# rpibout.net
KiCad netlist of a schematic drawn in EAGLE
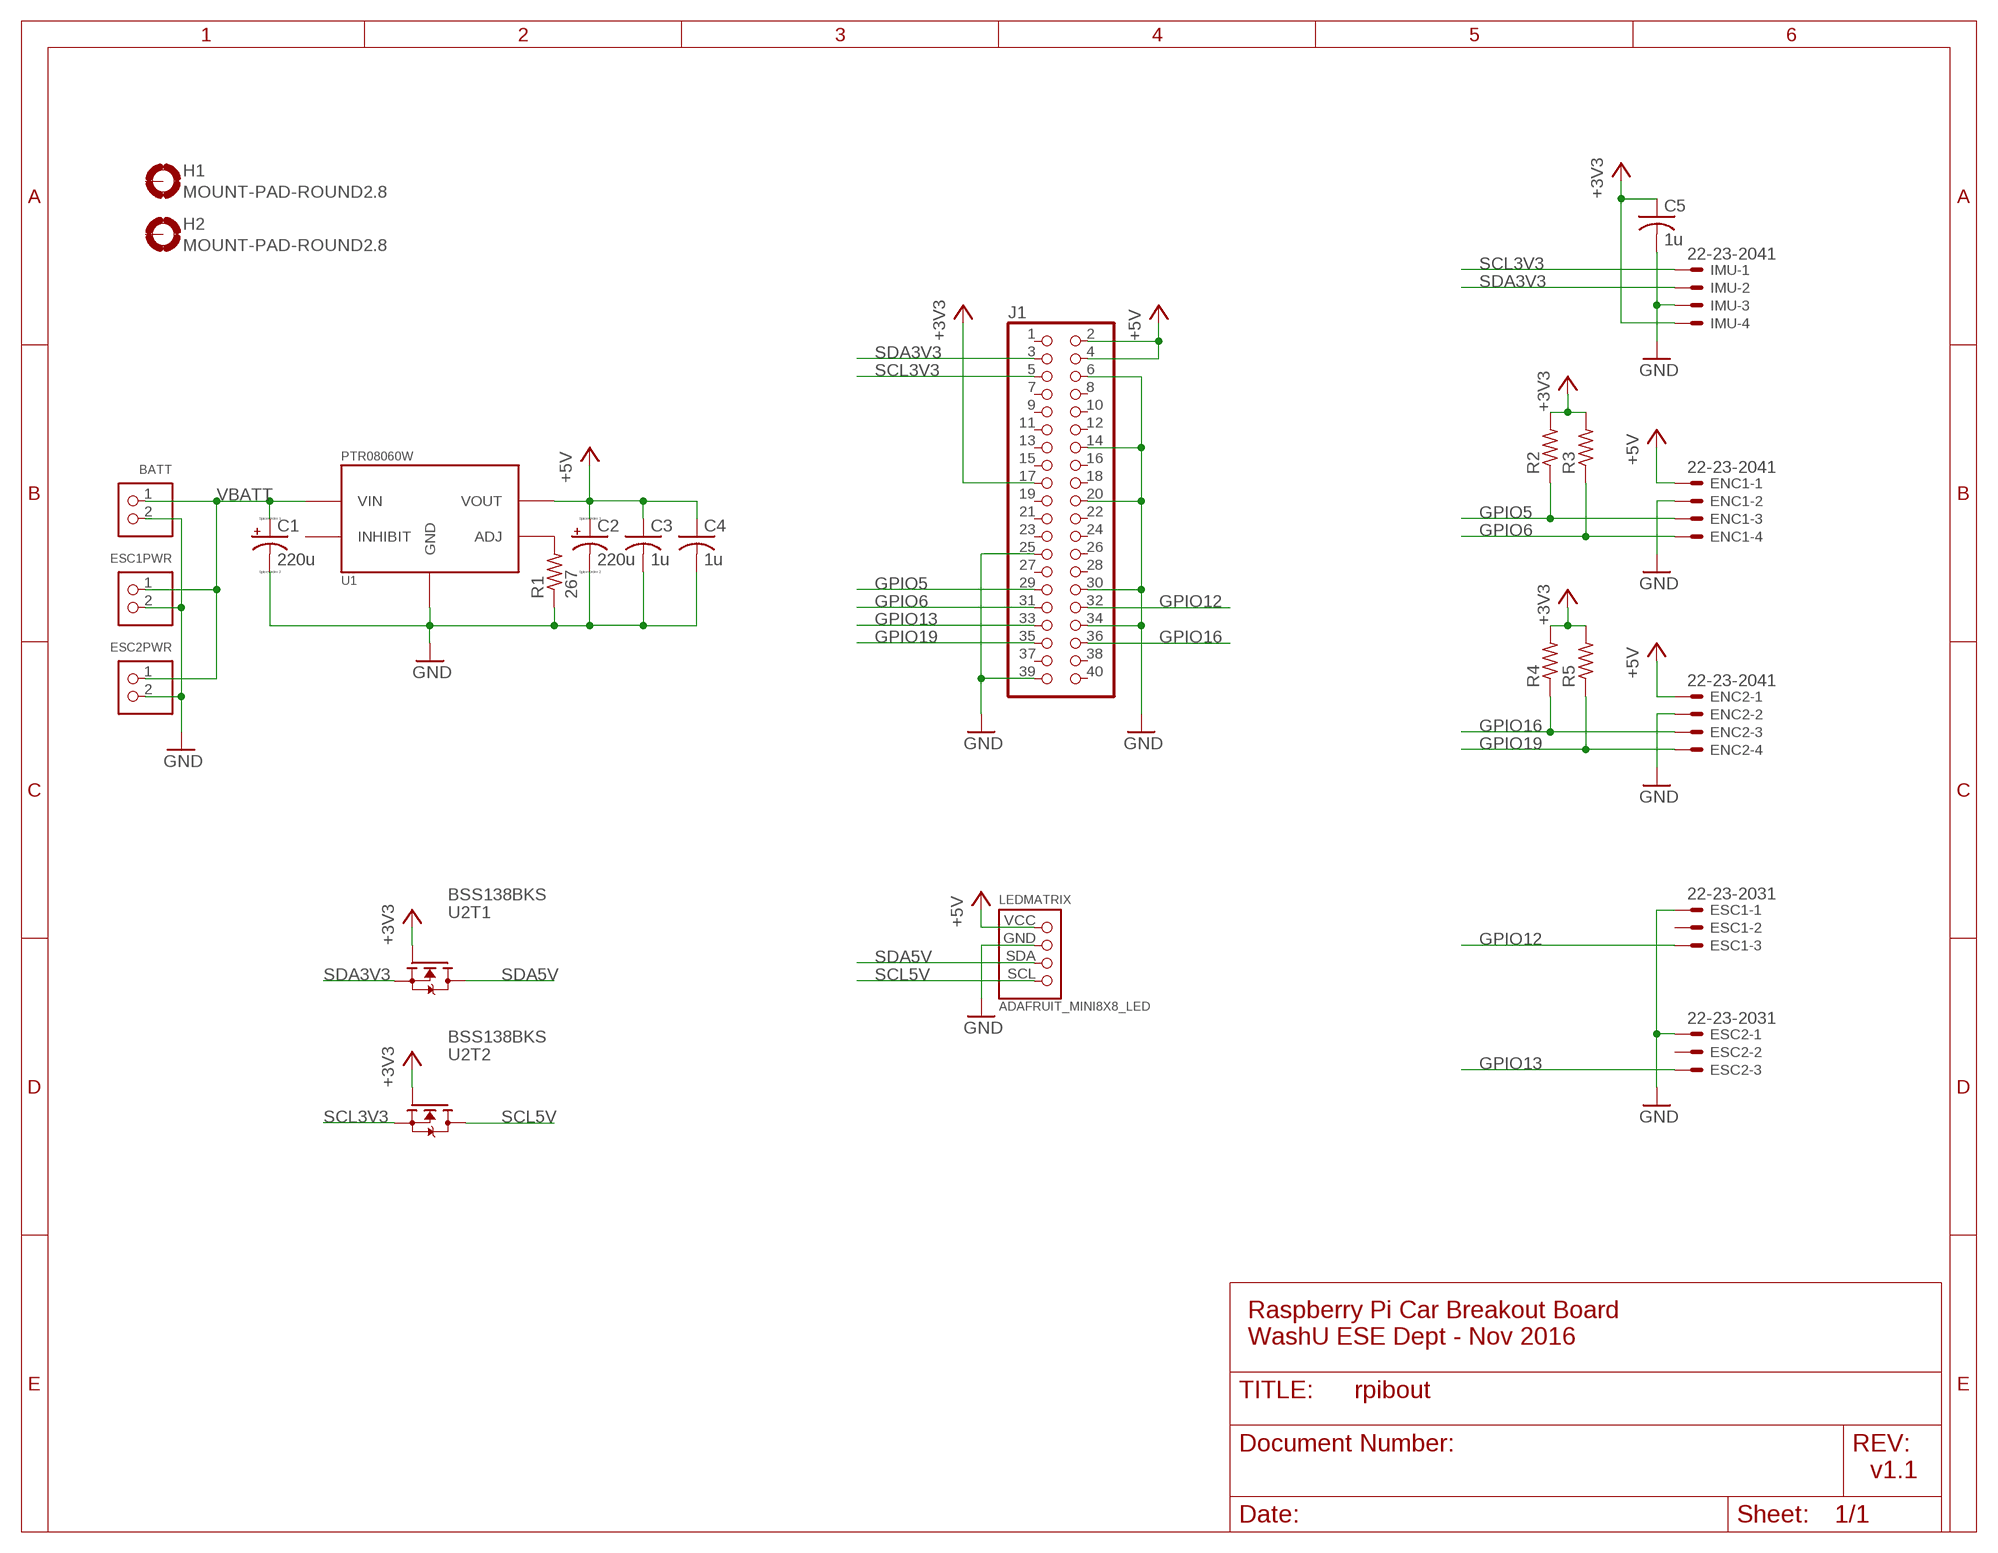
[diagram p0: schematic, sheet 1]

(export (version "E")
  (design (tool "Eeschema 10.0.6"))
  (components
    (comp (ref "BATT")
      (value "ULTRAFIT_2CIRC")
      (footprint "eagle-import:ULTRAFIT_2CIRC_RANGLE")
      (libsource (lib "eagle-import") (part "ULTRAFIT_2CIRC"))
    )
    (comp (ref "C1")
      (value "220u")
      (footprint "eagle-import:E3,5-8")
      (libsource (lib "eagle-import") (part "CPOL-USE3.5-8"))
    )
    (comp (ref "C2")
      (value "220u")
      (footprint "eagle-import:E3,5-8")
      (libsource (lib "eagle-import") (part "CPOL-USE3.5-8"))
    )
    (comp (ref "C3")
      (value "1u")
      (footprint "eagle-import:C1206")
      (libsource (lib "eagle-import") (part "C-USC1206"))
    )
    (comp (ref "C4")
      (value "1u")
      (footprint "eagle-import:C1206")
      (libsource (lib "eagle-import") (part "C-USC1206"))
    )
    (comp (ref "C5")
      (value "1u")
      (footprint "eagle-import:C1206")
      (libsource (lib "eagle-import") (part "C-USC1206"))
    )
    (comp (ref "ENC1")
      (value "22-23-2041")
      (footprint "eagle-import:22-23-2041")
      (fields (field (name "MF") "MOLEX"))
      (libsource (lib "eagle-import") (part "22-23-2041"))
    )
    (comp (ref "ENC2")
      (value "22-23-2041")
      (footprint "eagle-import:22-23-2041")
      (fields (field (name "MF") "MOLEX"))
      (libsource (lib "eagle-import") (part "22-23-2041"))
    )
    (comp (ref "ESC1")
      (value "22-23-2031")
      (footprint "eagle-import:22-23-2031")
      (fields (field (name "MF") "MOLEX"))
      (libsource (lib "eagle-import") (part "22-23-2031"))
    )
    (comp (ref "ESC1PWR")
      (value "ULTRAFIT_2CIRC")
      (footprint "eagle-import:ULTRAFIT_2CIRC_RANGLE")
      (libsource (lib "eagle-import") (part "ULTRAFIT_2CIRC"))
    )
    (comp (ref "ESC2")
      (value "22-23-2031")
      (footprint "eagle-import:22-23-2031")
      (fields (field (name "MF") "MOLEX"))
      (libsource (lib "eagle-import") (part "22-23-2031"))
    )
    (comp (ref "ESC2PWR")
      (value "ULTRAFIT_2CIRC")
      (footprint "eagle-import:ULTRAFIT_2CIRC_RANGLE")
      (libsource (lib "eagle-import") (part "ULTRAFIT_2CIRC"))
    )
    (comp (ref "H1")
      (value "MOUNT-PAD-ROUND2.8")
      (footprint "eagle-import:2,8-PAD")
      (libsource (lib "eagle-import") (part "MOUNT-PAD-ROUND2.8"))
    )
    (comp (ref "H2")
      (value "MOUNT-PAD-ROUND2.8")
      (footprint "eagle-import:2,8-PAD")
      (libsource (lib "eagle-import") (part "MOUNT-PAD-ROUND2.8"))
    )
    (comp (ref "IMU")
      (value "22-23-2041")
      (footprint "eagle-import:22-23-2041")
      (fields (field (name "MF") "MOLEX"))
      (libsource (lib "eagle-import") (part "22-23-2041"))
    )
    (comp (ref "J1")
      (value "PINHD-2X20")
      (footprint "eagle-import:2X20")
      (libsource (lib "eagle-import") (part "PINHD-2X20"))
    )
    (comp (ref "LEDMATRIX")
      (value "ADAFRUIT_MINI8X8_LED")
      (footprint "eagle-import:ADAFRUIT_MINI8X8_BACKPACK")
      (libsource (lib "eagle-import") (part "ADAFRUIT_MINI8X8_LED"))
    )
    (comp (ref "R1")
      (value "267")
      (footprint "eagle-import:R1206")
      (libsource (lib "eagle-import") (part "R-US_R1206"))
    )
    (comp (ref "R2")
      (value "R-US_R1206")
      (footprint "eagle-import:R1206")
      (libsource (lib "eagle-import") (part "R-US_R1206"))
    )
    (comp (ref "R3")
      (value "R-US_R1206")
      (footprint "eagle-import:R1206")
      (libsource (lib "eagle-import") (part "R-US_R1206"))
    )
    (comp (ref "R4")
      (value "R-US_R1206")
      (footprint "eagle-import:R1206")
      (libsource (lib "eagle-import") (part "R-US_R1206"))
    )
    (comp (ref "R5")
      (value "R-US_R1206")
      (footprint "eagle-import:R1206")
      (libsource (lib "eagle-import") (part "R-US_R1206"))
    )
    (comp (ref "U1")
      (value "PTR08060W")
      (footprint "eagle-import:EDP_MODULE")
      (libsource (lib "eagle-import") (part "PTR08060W"))
    )
    (comp (ref "U2")
      (value "BSS138BKS")
      (footprint "eagle-import:SOT363")
      (libsource (lib "eagle-import") (part "BSS138BKS"))
    )
  )
  (nets
    (net (code "1") (name "+3V3") (class "Default")
      (node (ref "C5") (pin "1") (pinfunction "1_1") (pintype "passive"))
      (node (ref "IMU") (pin "4") (pinfunction "S_4") (pintype "passive"))
      (node (ref "J1") (pin "17") (pinfunction "17_17") (pintype "passive"))
      (node (ref "R2") (pin "2") (pinfunction "2_2") (pintype "passive"))
      (node (ref "R3") (pin "2") (pinfunction "2_2") (pintype "passive"))
      (node (ref "R4") (pin "2") (pinfunction "2_2") (pintype "passive"))
      (node (ref "R5") (pin "2") (pinfunction "2_2") (pintype "passive"))
      (node (ref "U2") (pin "2") (pinfunction "G_2") (pintype "passive"))
      (node (ref "U2") (pin "5") (pinfunction "G_5") (pintype "passive"))
    )
    (net (code "2") (name "+5V") (class "Default")
      (node (ref "C2") (pin "+") (pinfunction "+_+") (pintype "passive"))
      (node (ref "C3") (pin "1") (pinfunction "1_1") (pintype "passive"))
      (node (ref "C4") (pin "1") (pinfunction "1_1") (pintype "passive"))
      (node (ref "ENC1") (pin "1") (pinfunction "S_1") (pintype "passive"))
      (node (ref "ENC2") (pin "1") (pinfunction "S_1") (pintype "passive"))
      (node (ref "J1") (pin "2") (pinfunction "2_2") (pintype "passive"))
      (node (ref "J1") (pin "4") (pinfunction "4_4") (pintype "passive"))
      (node (ref "LEDMATRIX") (pin "VCC") (pinfunction "VCC_VCC") (pintype "power_in"))
      (node (ref "U1") (pin "P4") (pinfunction "VOUT_P4") (pintype "power_in"))
    )
    (net (code "3") (name "/GPIO5") (class "Default")
      (node (ref "ENC1") (pin "3") (pinfunction "S_3") (pintype "passive"))
      (node (ref "J1") (pin "29") (pinfunction "29_29") (pintype "passive"))
      (node (ref "R2") (pin "1") (pinfunction "1_1") (pintype "passive"))
    )
    (net (code "4") (name "/GPIO6") (class "Default")
      (node (ref "ENC1") (pin "4") (pinfunction "S_4") (pintype "passive"))
      (node (ref "J1") (pin "31") (pinfunction "31_31") (pintype "passive"))
      (node (ref "R3") (pin "1") (pinfunction "1_1") (pintype "passive"))
    )
    (net (code "5") (name "/GPIO12") (class "Default")
      (node (ref "ESC1") (pin "3") (pinfunction "S_3") (pintype "passive"))
      (node (ref "J1") (pin "32") (pinfunction "32_32") (pintype "passive"))
    )
    (net (code "6") (name "/GPIO13") (class "Default")
      (node (ref "ESC2") (pin "3") (pinfunction "S_3") (pintype "passive"))
      (node (ref "J1") (pin "33") (pinfunction "33_33") (pintype "passive"))
    )
    (net (code "7") (name "/GPIO16") (class "Default")
      (node (ref "ENC2") (pin "3") (pinfunction "S_3") (pintype "passive"))
      (node (ref "J1") (pin "36") (pinfunction "36_36") (pintype "passive"))
      (node (ref "R4") (pin "1") (pinfunction "1_1") (pintype "passive"))
    )
    (net (code "8") (name "/GPIO19") (class "Default")
      (node (ref "ENC2") (pin "4") (pinfunction "S_4") (pintype "passive"))
      (node (ref "J1") (pin "35") (pinfunction "35_35") (pintype "passive"))
      (node (ref "R5") (pin "1") (pinfunction "1_1") (pintype "passive"))
    )
    (net (code "9") (name "/SCL3V3") (class "Default")
      (node (ref "IMU") (pin "1") (pinfunction "S_1") (pintype "passive"))
      (node (ref "J1") (pin "5") (pinfunction "5_5") (pintype "passive"))
      (node (ref "U2") (pin "4") (pinfunction "S_4") (pintype "passive"))
    )
    (net (code "10") (name "/SCL5V") (class "Default")
      (node (ref "LEDMATRIX") (pin "SCL") (pinfunction "SCL_SCL") (pintype "bidirectional"))
      (node (ref "U2") (pin "3") (pinfunction "D_3") (pintype "passive"))
    )
    (net (code "11") (name "/SDA3V3") (class "Default")
      (node (ref "IMU") (pin "2") (pinfunction "S_2") (pintype "passive"))
      (node (ref "J1") (pin "3") (pinfunction "3_3") (pintype "passive"))
      (node (ref "U2") (pin "1") (pinfunction "S_1") (pintype "passive"))
    )
    (net (code "12") (name "/SDA5V") (class "Default")
      (node (ref "LEDMATRIX") (pin "SDA") (pinfunction "SDA_SDA") (pintype "bidirectional"))
      (node (ref "U2") (pin "6") (pinfunction "D_6") (pintype "passive"))
    )
    (net (code "13") (name "/VBATT") (class "Default")
      (node (ref "BATT") (pin "1") (pinfunction "P1_1") (pintype "power_in"))
      (node (ref "C1") (pin "+") (pinfunction "+_+") (pintype "passive"))
      (node (ref "ESC1PWR") (pin "1") (pinfunction "P1_1") (pintype "power_in"))
      (node (ref "ESC2PWR") (pin "1") (pinfunction "P1_1") (pintype "power_in"))
      (node (ref "U1") (pin "P2") (pinfunction "VIN_P2") (pintype "power_in"))
    )
    (net (code "14") (name "GND") (class "Default")
      (node (ref "BATT") (pin "2") (pinfunction "P2_2") (pintype "power_in"))
      (node (ref "C1") (pin "-") (pinfunction "-_-") (pintype "passive"))
      (node (ref "C2") (pin "-") (pinfunction "-_-") (pintype "passive"))
      (node (ref "C3") (pin "2") (pinfunction "2_2") (pintype "passive"))
      (node (ref "C4") (pin "2") (pinfunction "2_2") (pintype "passive"))
      (node (ref "C5") (pin "2") (pinfunction "2_2") (pintype "passive"))
      (node (ref "ENC1") (pin "2") (pinfunction "S_2") (pintype "passive"))
      (node (ref "ENC2") (pin "2") (pinfunction "S_2") (pintype "passive"))
      (node (ref "ESC1") (pin "1") (pinfunction "S_1") (pintype "passive"))
      (node (ref "ESC1PWR") (pin "2") (pinfunction "P2_2") (pintype "power_in"))
      (node (ref "ESC2") (pin "1") (pinfunction "S_1") (pintype "passive"))
      (node (ref "ESC2PWR") (pin "2") (pinfunction "P2_2") (pintype "power_in"))
      (node (ref "IMU") (pin "3") (pinfunction "S_3") (pintype "passive"))
      (node (ref "J1") (pin "14") (pinfunction "14_14") (pintype "passive"))
      (node (ref "J1") (pin "20") (pinfunction "20_20") (pintype "passive"))
      (node (ref "J1") (pin "25") (pinfunction "25_25") (pintype "passive"))
      (node (ref "J1") (pin "30") (pinfunction "30_30") (pintype "passive"))
      (node (ref "J1") (pin "34") (pinfunction "34_34") (pintype "passive"))
      (node (ref "J1") (pin "39") (pinfunction "39_39") (pintype "passive"))
      (node (ref "J1") (pin "6") (pinfunction "6_6") (pintype "passive"))
      (node (ref "LEDMATRIX") (pin "GND") (pinfunction "GND_GND") (pintype "power_in"))
      (node (ref "R1") (pin "1") (pinfunction "1_1") (pintype "passive"))
      (node (ref "U1") (pin "P3") (pinfunction "GND_P3") (pintype "power_in"))
    )
    (net (code "15") (name "Net-(U1-ADJ)") (class "Default")
      (node (ref "R1") (pin "2") (pinfunction "2_2") (pintype "passive"))
      (node (ref "U1") (pin "P5") (pinfunction "ADJ_P5") (pintype "passive"))
    )
    (net (code "16") (name "unconnected-(ESC1B-S-Pad2)") (class "Default")
      (node (ref "ESC1") (pin "2") (pinfunction "S_2") (pintype "passive"))
    )
    (net (code "17") (name "unconnected-(ESC2B-S-Pad2)") (class "Default")
      (node (ref "ESC2") (pin "2") (pinfunction "S_2") (pintype "passive"))
    )
    (net (code "18") (name "unconnected-(H1-MOUNT-PadB2,8)") (class "Default")
      (node (ref "H1") (pin "B2,8") (pinfunction "MOUNT_B2,8") (pintype "passive"))
    )
    (net (code "19") (name "unconnected-(H2-MOUNT-PadB2,8)") (class "Default")
      (node (ref "H2") (pin "B2,8") (pinfunction "MOUNT_B2,8") (pintype "passive"))
    )
    (net (code "20") (name "unconnected-(J1-Pad1)") (class "Default")
      (node (ref "J1") (pin "1") (pinfunction "1_1") (pintype "passive"))
    )
    (net (code "21") (name "unconnected-(J1-Pad7)") (class "Default")
      (node (ref "J1") (pin "7") (pinfunction "7_7") (pintype "passive"))
    )
    (net (code "22") (name "unconnected-(J1-Pad8)") (class "Default")
      (node (ref "J1") (pin "8") (pinfunction "8_8") (pintype "passive"))
    )
    (net (code "23") (name "unconnected-(J1-Pad9)") (class "Default")
      (node (ref "J1") (pin "9") (pinfunction "9_9") (pintype "passive"))
    )
    (net (code "24") (name "unconnected-(J1-Pad10)") (class "Default")
      (node (ref "J1") (pin "10") (pinfunction "10_10") (pintype "passive"))
    )
    (net (code "25") (name "unconnected-(J1-Pad11)") (class "Default")
      (node (ref "J1") (pin "11") (pinfunction "11_11") (pintype "passive"))
    )
    (net (code "26") (name "unconnected-(J1-Pad12)") (class "Default")
      (node (ref "J1") (pin "12") (pinfunction "12_12") (pintype "passive"))
    )
    (net (code "27") (name "unconnected-(J1-Pad13)") (class "Default")
      (node (ref "J1") (pin "13") (pinfunction "13_13") (pintype "passive"))
    )
    (net (code "28") (name "unconnected-(J1-Pad15)") (class "Default")
      (node (ref "J1") (pin "15") (pinfunction "15_15") (pintype "passive"))
    )
    (net (code "29") (name "unconnected-(J1-Pad16)") (class "Default")
      (node (ref "J1") (pin "16") (pinfunction "16_16") (pintype "passive"))
    )
    (net (code "30") (name "unconnected-(J1-Pad18)") (class "Default")
      (node (ref "J1") (pin "18") (pinfunction "18_18") (pintype "passive"))
    )
    (net (code "31") (name "unconnected-(J1-Pad19)") (class "Default")
      (node (ref "J1") (pin "19") (pinfunction "19_19") (pintype "passive"))
    )
    (net (code "32") (name "unconnected-(J1-Pad21)") (class "Default")
      (node (ref "J1") (pin "21") (pinfunction "21_21") (pintype "passive"))
    )
    (net (code "33") (name "unconnected-(J1-Pad22)") (class "Default")
      (node (ref "J1") (pin "22") (pinfunction "22_22") (pintype "passive"))
    )
    (net (code "34") (name "unconnected-(J1-Pad23)") (class "Default")
      (node (ref "J1") (pin "23") (pinfunction "23_23") (pintype "passive"))
    )
    (net (code "35") (name "unconnected-(J1-Pad24)") (class "Default")
      (node (ref "J1") (pin "24") (pinfunction "24_24") (pintype "passive"))
    )
    (net (code "36") (name "unconnected-(J1-Pad26)") (class "Default")
      (node (ref "J1") (pin "26") (pinfunction "26_26") (pintype "passive"))
    )
    (net (code "37") (name "unconnected-(J1-Pad27)") (class "Default")
      (node (ref "J1") (pin "27") (pinfunction "27_27") (pintype "passive"))
    )
    (net (code "38") (name "unconnected-(J1-Pad28)") (class "Default")
      (node (ref "J1") (pin "28") (pinfunction "28_28") (pintype "passive"))
    )
    (net (code "39") (name "unconnected-(J1-Pad37)") (class "Default")
      (node (ref "J1") (pin "37") (pinfunction "37_37") (pintype "passive"))
    )
    (net (code "40") (name "unconnected-(J1-Pad38)") (class "Default")
      (node (ref "J1") (pin "38") (pinfunction "38_38") (pintype "passive"))
    )
    (net (code "41") (name "unconnected-(J1-Pad40)") (class "Default")
      (node (ref "J1") (pin "40") (pinfunction "40_40") (pintype "passive"))
    )
    (net (code "42") (name "unconnected-(U1-INHIBIT-PadP1)") (class "Default")
      (node (ref "U1") (pin "P1") (pinfunction "INHIBIT_P1") (pintype "open_collector"))
    )
  )
)
